# tda2030a_amplifier_kit.net
KiCad netlist of a schematic drawn in EAGLE
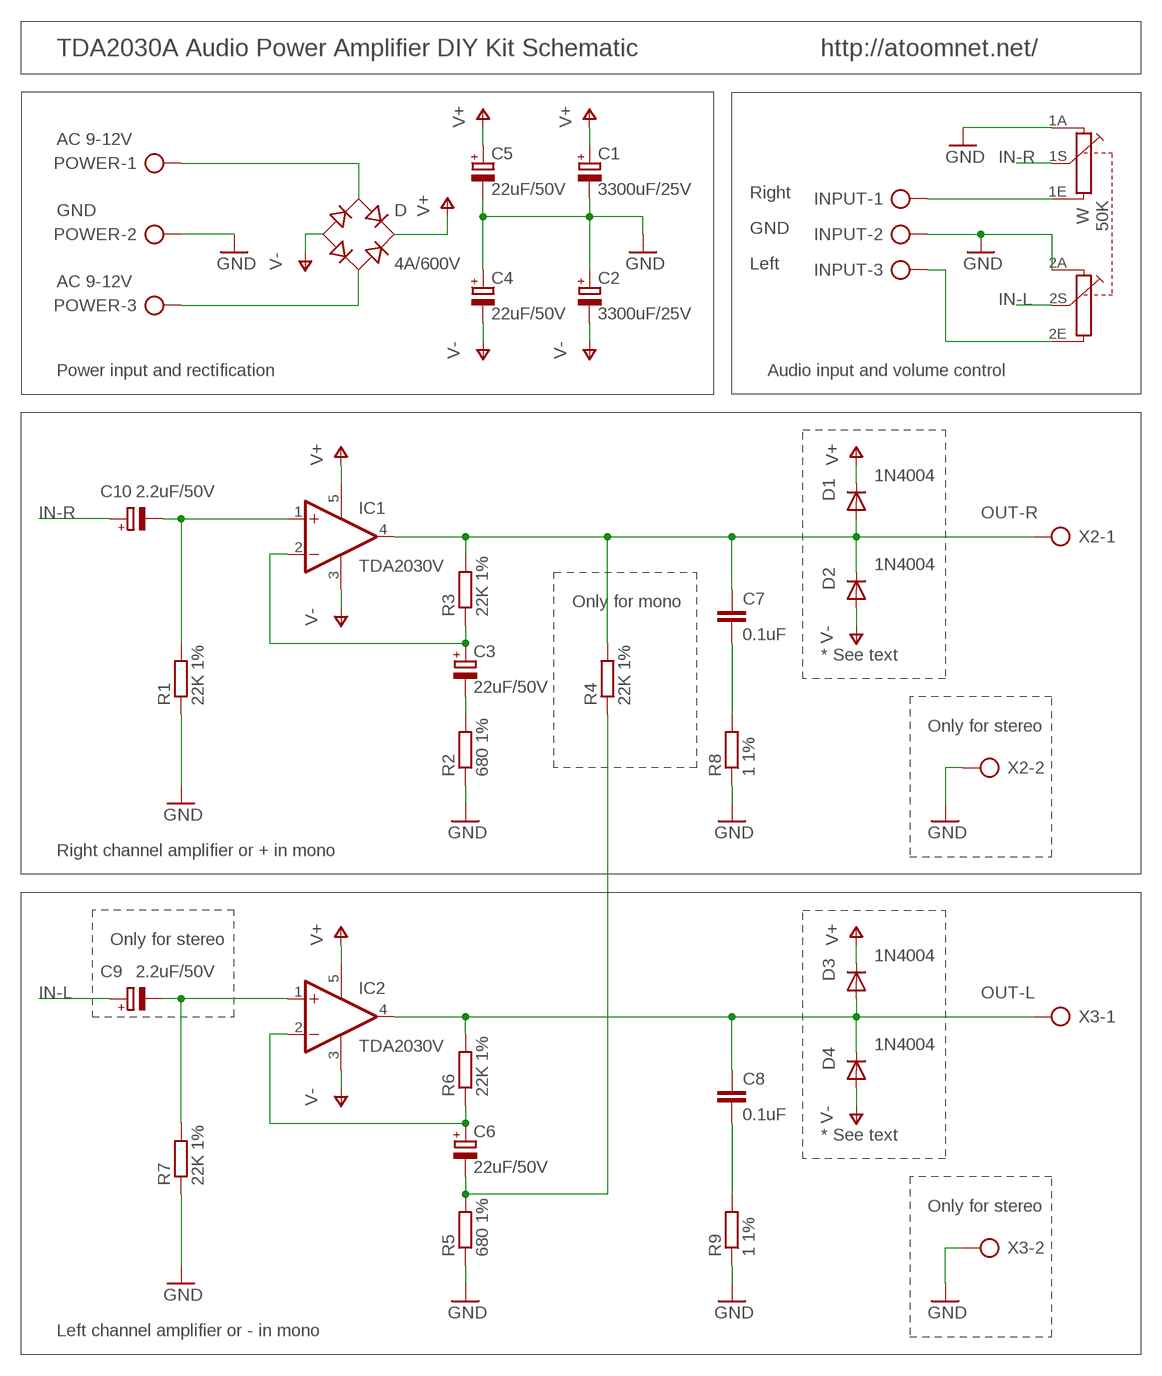
[diagram p0: schematic, sheet 1]

(export (version "E")
  (design (tool "Eeschema 10.0.6"))
  (components
    (comp (ref "C1")
      (value "3300uF/25V")
      (footprint "eagle-import:E7,5-18")
      (libsource (lib "eagle-import") (part "CPOL-EUE7.5-18"))
    )
    (comp (ref "C2")
      (value "3300uF/25V")
      (footprint "eagle-import:E7,5-18")
      (libsource (lib "eagle-import") (part "CPOL-EUE7.5-18"))
    )
    (comp (ref "C3")
      (value "22uF/50V")
      (footprint "eagle-import:E2-5")
      (libsource (lib "eagle-import") (part "CPOL-EUE2-5"))
    )
    (comp (ref "C4")
      (value "22uF/50V")
      (footprint "eagle-import:E2-5")
      (libsource (lib "eagle-import") (part "CPOL-EUE2-5"))
    )
    (comp (ref "C5")
      (value "22uF/50V")
      (footprint "eagle-import:E2-5")
      (libsource (lib "eagle-import") (part "CPOL-EUE2-5"))
    )
    (comp (ref "C6")
      (value "22uF/50V")
      (footprint "eagle-import:E2-5")
      (libsource (lib "eagle-import") (part "CPOL-EUE2-5"))
    )
    (comp (ref "C7")
      (value "0.1uF")
      (footprint "eagle-import:C050-030X075")
      (libsource (lib "eagle-import") (part "C-EU050-030X075"))
    )
    (comp (ref "C8")
      (value "0.1uF")
      (footprint "eagle-import:C050-030X075")
      (libsource (lib "eagle-import") (part "C-EU050-030X075"))
    )
    (comp (ref "C9")
      (value "2.2uF/50V")
      (footprint "eagle-import:E2-5")
      (libsource (lib "eagle-import") (part "CPOL-EUE2-5"))
    )
    (comp (ref "C10")
      (value "2.2uF/50V")
      (footprint "eagle-import:E2-5")
      (libsource (lib "eagle-import") (part "CPOL-EUE2-5"))
    )
    (comp (ref "D")
      (value "4A/600V")
      (footprint "eagle-import:FBU4")
      (libsource (lib "eagle-import") (part "RECTIFIER-FBU4"))
    )
    (comp (ref "D1")
      (value "1N4004")
      (footprint "eagle-import:DO41-10")
      (libsource (lib "eagle-import") (part "1N4004"))
    )
    (comp (ref "D2")
      (value "1N4004")
      (footprint "eagle-import:DO41-10")
      (libsource (lib "eagle-import") (part "1N4004"))
    )
    (comp (ref "D3")
      (value "1N4004")
      (footprint "eagle-import:DO41-10")
      (libsource (lib "eagle-import") (part "1N4004"))
    )
    (comp (ref "D4")
      (value "1N4004")
      (footprint "eagle-import:DO41-10")
      (libsource (lib "eagle-import") (part "1N4004"))
    )
    (comp (ref "IC1")
      (value "TDA2030V")
      (footprint "eagle-import:CB360")
      (libsource (lib "eagle-import") (part "TDA2030V"))
    )
    (comp (ref "IC2")
      (value "TDA2030V")
      (footprint "eagle-import:CB360")
      (libsource (lib "eagle-import") (part "TDA2030V"))
    )
    (comp (ref "INPUT")
      (value "AK500/3")
      (footprint "eagle-import:AK500_3")
      (libsource (lib "eagle-import") (part "AK500/3"))
    )
    (comp (ref "POWER")
      (value "AK500/3")
      (footprint "eagle-import:AK500_3")
      (libsource (lib "eagle-import") (part "AK500/3"))
    )
    (comp (ref "R1")
      (value "22K 1%")
      (footprint "eagle-import:0207_10")
      (libsource (lib "eagle-import") (part "R-EU_0207/10"))
    )
    (comp (ref "R2")
      (value "680 1%")
      (footprint "eagle-import:0207_10")
      (libsource (lib "eagle-import") (part "R-EU_0207/10"))
    )
    (comp (ref "R3")
      (value "22K 1%")
      (footprint "eagle-import:0207_10")
      (libsource (lib "eagle-import") (part "R-EU_0207/10"))
    )
    (comp (ref "R4")
      (value "22K 1%")
      (footprint "eagle-import:0207_10")
      (libsource (lib "eagle-import") (part "R-EU_0207/10"))
    )
    (comp (ref "R5")
      (value "680 1%")
      (footprint "eagle-import:0207_10")
      (libsource (lib "eagle-import") (part "R-EU_0207/10"))
    )
    (comp (ref "R6")
      (value "22K 1%")
      (footprint "eagle-import:0207_10")
      (libsource (lib "eagle-import") (part "R-EU_0207/10"))
    )
    (comp (ref "R7")
      (value "22K 1%")
      (footprint "eagle-import:0207_10")
      (libsource (lib "eagle-import") (part "R-EU_0207/10"))
    )
    (comp (ref "R8")
      (value "1 1%")
      (footprint "eagle-import:0207_10")
      (libsource (lib "eagle-import") (part "R-EU_0207/10"))
    )
    (comp (ref "R9")
      (value "1 1%")
      (footprint "eagle-import:0207_10")
      (libsource (lib "eagle-import") (part "R-EU_0207/10"))
    )
    (comp (ref "W")
      (value "50K")
      (footprint "eagle-import:PC16D")
      (libsource (lib "eagle-import") (part "PC16D"))
    )
    (comp (ref "X2")
      (value "AK500/2")
      (footprint "eagle-import:AK500_2")
      (libsource (lib "eagle-import") (part "AK500/2"))
    )
    (comp (ref "X3")
      (value "AK500/2")
      (footprint "eagle-import:AK500_2")
      (libsource (lib "eagle-import") (part "AK500/2"))
    )
  )
  (nets
    (net (code "1") (name "/IN-L") (class "Default")
      (node (ref "C9") (pin "+") (pinfunction "+_+") (pintype "passive"))
      (node (ref "W") (pin "2S") (pinfunction "2S_2S") (pintype "passive"))
    )
    (net (code "2") (name "/IN-R") (class "Default")
      (node (ref "C10") (pin "+") (pinfunction "+_+") (pintype "passive"))
      (node (ref "W") (pin "1S") (pinfunction "1S_1S") (pintype "passive"))
    )
    (net (code "3") (name "/OUT-L") (class "Default")
      (node (ref "C8") (pin "1") (pinfunction "1_1") (pintype "passive"))
      (node (ref "D3") (pin "A") (pinfunction "A_A") (pintype "passive"))
      (node (ref "D4") (pin "C") (pinfunction "C_C") (pintype "passive"))
      (node (ref "IC2") (pin "4") (pinfunction "OUT_4") (pintype "output"))
      (node (ref "R6") (pin "2") (pinfunction "2_2") (pintype "passive"))
      (node (ref "X3") (pin "1") (pinfunction "KL_1") (pintype "passive"))
    )
    (net (code "4") (name "/OUT-R") (class "Default")
      (node (ref "C7") (pin "1") (pinfunction "1_1") (pintype "passive"))
      (node (ref "D1") (pin "A") (pinfunction "A_A") (pintype "passive"))
      (node (ref "D2") (pin "C") (pinfunction "C_C") (pintype "passive"))
      (node (ref "IC1") (pin "4") (pinfunction "OUT_4") (pintype "output"))
      (node (ref "R3") (pin "2") (pinfunction "2_2") (pintype "passive"))
      (node (ref "R4") (pin "2") (pinfunction "2_2") (pintype "passive"))
      (node (ref "X2") (pin "1") (pinfunction "KL_1") (pintype "passive"))
    )
    (net (code "5") (name "GND") (class "Default")
      (node (ref "C1") (pin "-") (pinfunction "-_-") (pintype "passive"))
      (node (ref "C2") (pin "+") (pinfunction "+_+") (pintype "passive"))
      (node (ref "C4") (pin "+") (pinfunction "+_+") (pintype "passive"))
      (node (ref "C5") (pin "-") (pinfunction "-_-") (pintype "passive"))
      (node (ref "INPUT") (pin "2") (pinfunction "KL_2") (pintype "passive"))
      (node (ref "POWER") (pin "2") (pinfunction "KL_2") (pintype "passive"))
      (node (ref "R1") (pin "1") (pinfunction "1_1") (pintype "passive"))
      (node (ref "R2") (pin "1") (pinfunction "1_1") (pintype "passive"))
      (node (ref "R5") (pin "1") (pinfunction "1_1") (pintype "passive"))
      (node (ref "R7") (pin "1") (pinfunction "1_1") (pintype "passive"))
      (node (ref "R8") (pin "1") (pinfunction "1_1") (pintype "passive"))
      (node (ref "R9") (pin "1") (pinfunction "1_1") (pintype "passive"))
      (node (ref "W") (pin "1A") (pinfunction "1A_1A") (pintype "passive"))
      (node (ref "W") (pin "2A") (pinfunction "2A_2A") (pintype "passive"))
      (node (ref "X2") (pin "2") (pinfunction "KL_2") (pintype "passive"))
      (node (ref "X3") (pin "2") (pinfunction "KL_2") (pintype "passive"))
    )
    (net (code "6") (name "Net-(C3-Pad-)") (class "Default")
      (node (ref "C3") (pin "-") (pinfunction "-_-") (pintype "passive"))
      (node (ref "R2") (pin "2") (pinfunction "2_2") (pintype "passive"))
    )
    (net (code "7") (name "Net-(C6-Pad-)") (class "Default")
      (node (ref "C6") (pin "-") (pinfunction "-_-") (pintype "passive"))
      (node (ref "R4") (pin "1") (pinfunction "1_1") (pintype "passive"))
      (node (ref "R5") (pin "2") (pinfunction "2_2") (pintype "passive"))
    )
    (net (code "8") (name "Net-(C7-Pad2)") (class "Default")
      (node (ref "C7") (pin "2") (pinfunction "2_2") (pintype "passive"))
      (node (ref "R8") (pin "2") (pinfunction "2_2") (pintype "passive"))
    )
    (net (code "9") (name "Net-(C8-Pad2)") (class "Default")
      (node (ref "C8") (pin "2") (pinfunction "2_2") (pintype "passive"))
      (node (ref "R9") (pin "2") (pinfunction "2_2") (pintype "passive"))
    )
    (net (code "10") (name "Net-(IC1-+IN)") (class "Default")
      (node (ref "C10") (pin "-") (pinfunction "-_-") (pintype "passive"))
      (node (ref "IC1") (pin "1") (pinfunction "+IN_1") (pintype "input"))
      (node (ref "R1") (pin "2") (pinfunction "2_2") (pintype "passive"))
    )
    (net (code "11") (name "Net-(IC1--IN)") (class "Default")
      (node (ref "C3") (pin "+") (pinfunction "+_+") (pintype "passive"))
      (node (ref "IC1") (pin "2") (pinfunction "-IN_2") (pintype "input"))
      (node (ref "R3") (pin "1") (pinfunction "1_1") (pintype "passive"))
    )
    (net (code "12") (name "Net-(IC2-+IN)") (class "Default")
      (node (ref "C9") (pin "-") (pinfunction "-_-") (pintype "passive"))
      (node (ref "IC2") (pin "1") (pinfunction "+IN_1") (pintype "input"))
      (node (ref "R7") (pin "2") (pinfunction "2_2") (pintype "passive"))
    )
    (net (code "13") (name "Net-(IC2--IN)") (class "Default")
      (node (ref "C6") (pin "+") (pinfunction "+_+") (pintype "passive"))
      (node (ref "IC2") (pin "2") (pinfunction "-IN_2") (pintype "input"))
      (node (ref "R6") (pin "1") (pinfunction "1_1") (pintype "passive"))
    )
    (net (code "14") (name "Net-(INPUTA-KL)") (class "Default")
      (node (ref "INPUT") (pin "1") (pinfunction "KL_1") (pintype "passive"))
      (node (ref "W") (pin "1E") (pinfunction "1E_1E") (pintype "passive"))
    )
    (net (code "15") (name "Net-(INPUTC-KL)") (class "Default")
      (node (ref "INPUT") (pin "3") (pinfunction "KL_3") (pintype "passive"))
      (node (ref "W") (pin "2E") (pinfunction "2E_2E") (pintype "passive"))
    )
    (net (code "16") (name "Net-(POWERA-KL)") (class "Default")
      (node (ref "D") (pin "AC1") (pinfunction "AC1_AC1") (pintype "passive"))
      (node (ref "POWER") (pin "1") (pinfunction "KL_1") (pintype "passive"))
    )
    (net (code "17") (name "Net-(POWERC-KL)") (class "Default")
      (node (ref "D") (pin "AC2") (pinfunction "AC2_AC2") (pintype "passive"))
      (node (ref "POWER") (pin "3") (pinfunction "KL_3") (pintype "passive"))
    )
    (net (code "18") (name "V+") (class "Default")
      (node (ref "C1") (pin "+") (pinfunction "+_+") (pintype "passive"))
      (node (ref "C5") (pin "+") (pinfunction "+_+") (pintype "passive"))
      (node (ref "D") (pin "+") (pinfunction "+_+") (pintype "passive"))
      (node (ref "D1") (pin "C") (pinfunction "C_C") (pintype "passive"))
      (node (ref "D3") (pin "C") (pinfunction "C_C") (pintype "passive"))
      (node (ref "IC1") (pin "5") (pinfunction "V+_5") (pintype "power_in"))
      (node (ref "IC2") (pin "5") (pinfunction "V+_5") (pintype "power_in"))
    )
    (net (code "19") (name "V-") (class "Default")
      (node (ref "C2") (pin "-") (pinfunction "-_-") (pintype "passive"))
      (node (ref "C4") (pin "-") (pinfunction "-_-") (pintype "passive"))
      (node (ref "D") (pin "-") (pinfunction "-_-") (pintype "passive"))
      (node (ref "D2") (pin "A") (pinfunction "A_A") (pintype "passive"))
      (node (ref "D4") (pin "A") (pinfunction "A_A") (pintype "passive"))
      (node (ref "IC1") (pin "3") (pinfunction "GND_3") (pintype "power_in"))
      (node (ref "IC2") (pin "3") (pinfunction "GND_3") (pintype "power_in"))
    )
  )
)
